# lid.net
KiCad netlist of a schematic drawn in EAGLE
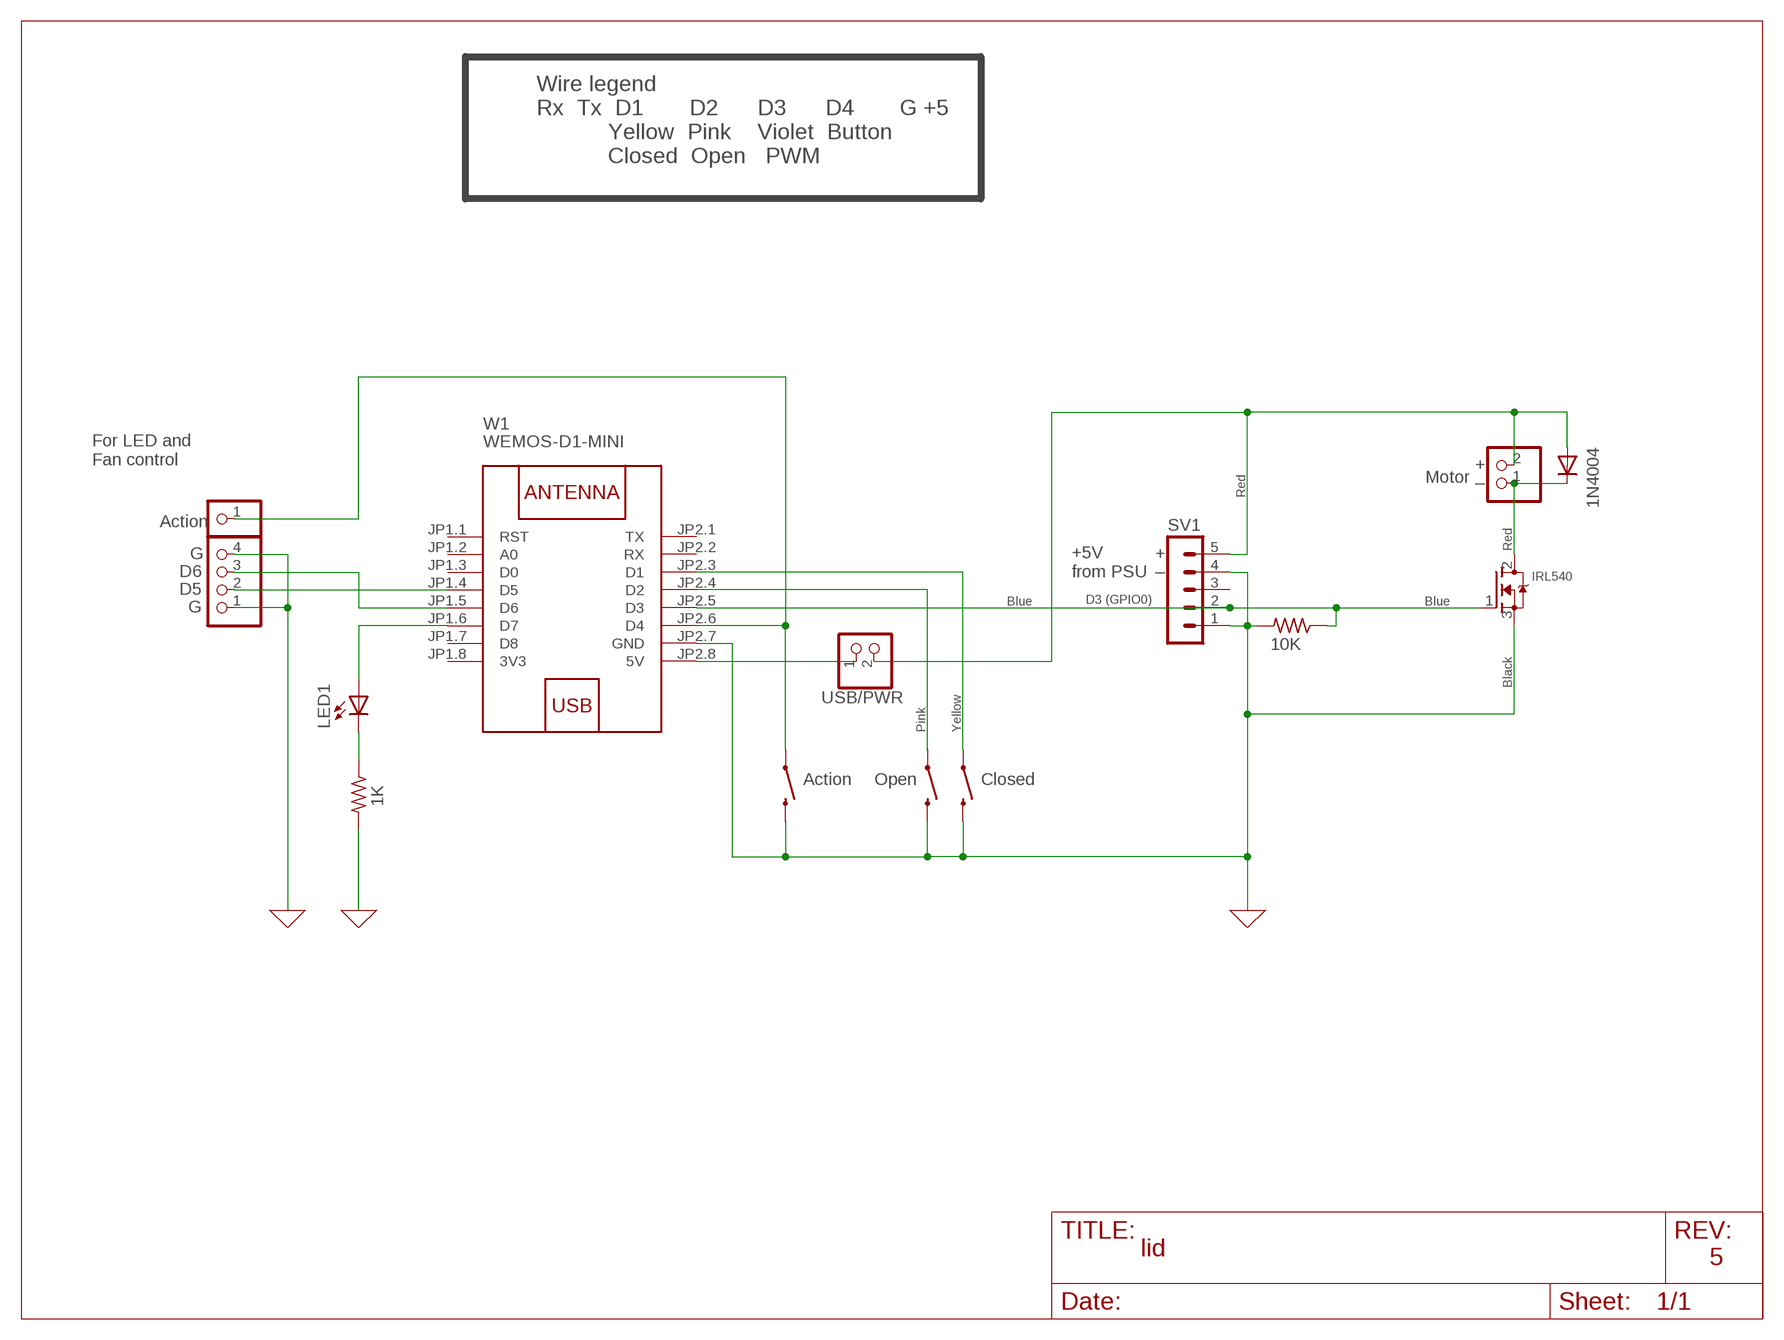
[diagram p0: schematic, sheet 1]

(export (version "E")
  (design (tool "Eeschema 10.0.6"))
  (components
    (comp (ref "ACTION")
      (value "MOMENTARY-SWITCH-SPST-PTH-6.0MM")
      (footprint "eagle-import:TACTILE_SWITCH_PTH_6.0MM")
      (libsource (lib "eagle-import") (part "MOMENTARY-SWITCH-SPST-PTH-6.0MM"))
    )
    (comp (ref "D1")
      (value "1N4004")
      (footprint "eagle-import:DO41-10")
      (libsource (lib "eagle-import") (part "1N4004"))
    )
    (comp (ref "JP1")
      (value "PINHD-1X1")
      (footprint "eagle-import:1X01")
      (libsource (lib "eagle-import") (part "PINHD-1X1"))
    )
    (comp (ref "JP3")
      (value "PINHD-1X2")
      (footprint "eagle-import:1X02")
      (libsource (lib "eagle-import") (part "PINHD-1X2"))
    )
    (comp (ref "JP4")
      (value "PINHD-1X4")
      (footprint "eagle-import:1X04")
      (libsource (lib "eagle-import") (part "PINHD-1X4"))
    )
    (comp (ref "LED1")
      (value "LED5MM")
      (footprint "eagle-import:LED5MM")
      (libsource (lib "eagle-import") (part "LED5MM"))
    )
    (comp (ref "Q1")
      (value "IRL540")
      (footprint "eagle-import:TO220V")
      (libsource (lib "eagle-import") (part "MOSFET-NGDS_TO220V"))
    )
    (comp (ref "R1")
      (value "1K")
      (footprint "eagle-import:0207_10")
      (libsource (lib "eagle-import") (part "R-US_0207/10"))
    )
    (comp (ref "R4")
      (value "10K")
      (footprint "eagle-import:0207_10")
      (libsource (lib "eagle-import") (part "R-US_0207/10"))
    )
    (comp (ref "S1")
      (value "MOMENTARY-SWITCH-SPST-PTH-6.0MM")
      (footprint "eagle-import:TACTILE_SWITCH_PTH_6.0MM")
      (libsource (lib "eagle-import") (part "MOMENTARY-SWITCH-SPST-PTH-6.0MM"))
    )
    (comp (ref "S2")
      (value "MOMENTARY-SWITCH-SPST-PTH-6.0MM")
      (footprint "eagle-import:TACTILE_SWITCH_PTH_6.0MM")
      (libsource (lib "eagle-import") (part "MOMENTARY-SWITCH-SPST-PTH-6.0MM"))
    )
    (comp (ref "SV1")
      (value "MA05-1")
      (footprint "eagle-import:MA05-1")
      (libsource (lib "eagle-import") (part "MA05-1"))
    )
    (comp (ref "USB/PWR")
      (value "PINHD-1X2")
      (footprint "eagle-import:1X02")
      (libsource (lib "eagle-import") (part "PINHD-1X2"))
    )
    (comp (ref "W1")
      (value "WEMOS-D1-MINI")
      (footprint "eagle-import:WEMOS-D1-MINI")
      (libsource (lib "eagle-import") (part "WEMOS-D1-MINI"))
    )
  )
  (nets
    (net (code "1") (name "/3V3") (class "Default")
      (node (ref "W1") (pin "JP1.8") (pinfunction "3V3_JP1.8") (pintype "power_in"))
    )
    (net (code "2") (name "GND") (class "Default")
      (node (ref "ACTION") (pin "3") (pinfunction "2_3") (pintype "passive"))
      (node (ref "JP4") (pin "1") (pinfunction "1_1") (pintype "passive"))
      (node (ref "JP4") (pin "4") (pinfunction "4_4") (pintype "passive"))
      (node (ref "Q1") (pin "3") (pinfunction "S_3") (pintype "bidirectional"))
      (node (ref "R1") (pin "2") (pinfunction "2_2") (pintype "passive"))
      (node (ref "R4") (pin "2") (pinfunction "2_2") (pintype "passive"))
      (node (ref "S1") (pin "3") (pinfunction "2_3") (pintype "passive"))
      (node (ref "S2") (pin "3") (pinfunction "2_3") (pintype "passive"))
      (node (ref "SV1") (pin "1") (pinfunction "1_1") (pintype "passive"))
      (node (ref "SV1") (pin "4") (pinfunction "4_4") (pintype "passive"))
      (node (ref "W1") (pin "JP2.7") (pinfunction "GND_JP2.7") (pintype "power_in"))
    )
    (net (code "3") (name "Net-(D1-PadA)") (class "Default")
      (node (ref "D1") (pin "A") (pinfunction "A_A") (pintype "passive"))
      (node (ref "JP3") (pin "2") (pinfunction "2_2") (pintype "passive"))
      (node (ref "SV1") (pin "5") (pinfunction "5_5") (pintype "passive"))
      (node (ref "USB/PWR") (pin "2") (pinfunction "2_2") (pintype "passive"))
    )
    (net (code "4") (name "Net-(LED1-C)") (class "Default")
      (node (ref "LED1") (pin "K") (pinfunction "C_K") (pintype "passive"))
      (node (ref "R1") (pin "1") (pinfunction "1_1") (pintype "passive"))
    )
    (net (code "5") (name "Net-(Q1-D)") (class "Default")
      (node (ref "D1") (pin "C") (pinfunction "C_C") (pintype "passive"))
      (node (ref "JP3") (pin "1") (pinfunction "1_1") (pintype "passive"))
      (node (ref "Q1") (pin "2") (pinfunction "D_2") (pintype "bidirectional"))
    )
    (net (code "6") (name "Net-(Q1-G)") (class "Default")
      (node (ref "Q1") (pin "1") (pinfunction "G_1") (pintype "bidirectional"))
      (node (ref "R4") (pin "1") (pinfunction "1_1") (pintype "passive"))
      (node (ref "SV1") (pin "2") (pinfunction "2_2") (pintype "passive"))
      (node (ref "W1") (pin "JP2.5") (pinfunction "D3_JP2.5") (pintype "bidirectional"))
    )
    (net (code "7") (name "Net-(W1-5V)") (class "Default")
      (node (ref "USB/PWR") (pin "1") (pinfunction "1_1") (pintype "passive"))
      (node (ref "W1") (pin "JP2.8") (pinfunction "5V_JP2.8") (pintype "power_in"))
    )
    (net (code "8") (name "Net-(W1-D1)") (class "Default")
      (node (ref "S2") (pin "1") (pinfunction "1_1") (pintype "passive"))
      (node (ref "W1") (pin "JP2.3") (pinfunction "D1_JP2.3") (pintype "bidirectional"))
    )
    (net (code "9") (name "Net-(W1-D2)") (class "Default")
      (node (ref "S1") (pin "1") (pinfunction "1_1") (pintype "passive"))
      (node (ref "W1") (pin "JP2.4") (pinfunction "D2_JP2.4") (pintype "bidirectional"))
    )
    (net (code "10") (name "Net-(W1-D4)") (class "Default")
      (node (ref "ACTION") (pin "1") (pinfunction "1_1") (pintype "passive"))
      (node (ref "JP1") (pin "1") (pinfunction "1_1") (pintype "passive"))
      (node (ref "W1") (pin "JP2.6") (pinfunction "D4_JP2.6") (pintype "bidirectional"))
    )
    (net (code "11") (name "Net-(W1-D5)") (class "Default")
      (node (ref "JP4") (pin "2") (pinfunction "2_2") (pintype "passive"))
      (node (ref "W1") (pin "JP1.4") (pinfunction "D5_JP1.4") (pintype "bidirectional"))
    )
    (net (code "12") (name "Net-(W1-D6)") (class "Default")
      (node (ref "JP4") (pin "3") (pinfunction "3_3") (pintype "passive"))
      (node (ref "W1") (pin "JP1.5") (pinfunction "D6_JP1.5") (pintype "bidirectional"))
    )
    (net (code "13") (name "Net-(W1-D7)") (class "Default")
      (node (ref "LED1") (pin "A") (pinfunction "A_A") (pintype "passive"))
      (node (ref "W1") (pin "JP1.6") (pinfunction "D7_JP1.6") (pintype "bidirectional"))
    )
    (net (code "14") (name "unconnected-(SV1-Pad3)") (class "Default")
      (node (ref "SV1") (pin "3") (pinfunction "3_3") (pintype "passive"))
    )
    (net (code "15") (name "unconnected-(W1-A0-PadJP1.2)") (class "Default")
      (node (ref "W1") (pin "JP1.2") (pinfunction "A0_JP1.2") (pintype "bidirectional"))
    )
    (net (code "16") (name "unconnected-(W1-D0-PadJP1.3)") (class "Default")
      (node (ref "W1") (pin "JP1.3") (pinfunction "D0_JP1.3") (pintype "bidirectional"))
    )
    (net (code "17") (name "unconnected-(W1-D8-PadJP1.7)") (class "Default")
      (node (ref "W1") (pin "JP1.7") (pinfunction "D8_JP1.7") (pintype "bidirectional"))
    )
    (net (code "18") (name "unconnected-(W1-RST-PadJP1.1)") (class "Default")
      (node (ref "W1") (pin "JP1.1") (pinfunction "RST_JP1.1") (pintype "bidirectional"))
    )
    (net (code "19") (name "unconnected-(W1-RX-PadJP2.2)") (class "Default")
      (node (ref "W1") (pin "JP2.2") (pinfunction "RX_JP2.2") (pintype "bidirectional"))
    )
    (net (code "20") (name "unconnected-(W1-TX-PadJP2.1)") (class "Default")
      (node (ref "W1") (pin "JP2.1") (pinfunction "TX_JP2.1") (pintype "bidirectional"))
    )
  )
)
